# quasi_nano_led.net
KiCad netlist of a schematic drawn in EAGLE
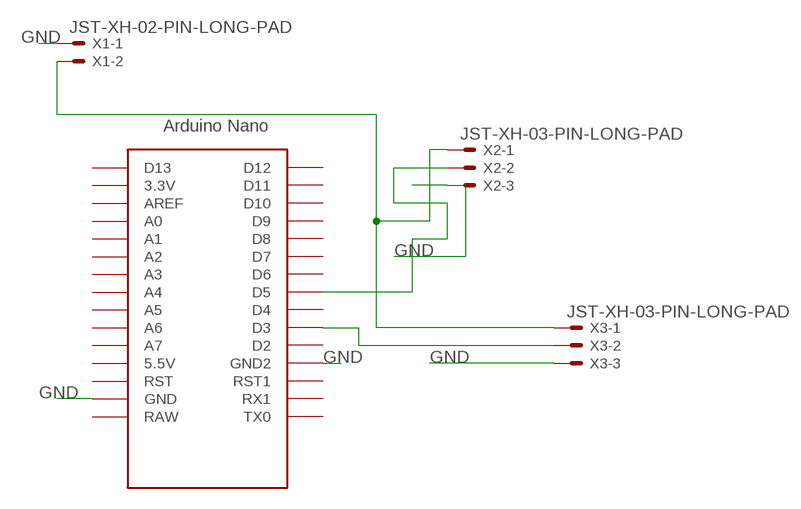
[diagram p0: schematic, sheet 1]

(export (version "E")
  (design (tool "Eeschema 10.0.6"))
  (components
    (comp (ref "U$1")
      (value "NANO")
      (footprint "eagle-import:NANO")
      (libsource (lib "eagle-import") (part "NANO"))
    )
    (comp (ref "X1")
      (value "JST-XH-02-PIN-LONG-PAD")
      (footprint "eagle-import:JST-XH-02-PACKAGE-LONG-PAD")
      (libsource (lib "eagle-import") (part "JST-XH-02-PIN-LONG-PAD"))
    )
    (comp (ref "X2")
      (value "JST-XH-03-PIN-LONG-PAD")
      (footprint "eagle-import:JST-XH-03-PACKAGE-LONG-PAD")
      (libsource (lib "eagle-import") (part "JST-XH-03-PIN-LONG-PAD"))
    )
    (comp (ref "X3")
      (value "JST-XH-03-PIN-LONG-PAD")
      (footprint "eagle-import:JST-XH-03-PACKAGE-LONG-PAD")
      (libsource (lib "eagle-import") (part "JST-XH-03-PIN-LONG-PAD"))
    )
  )
  (nets
    (net (code "1") (name "/GND") (class "Default")
      (node (ref "U$1") (pin "GND") (pinfunction "GND_GND") (pintype "bidirectional"))
      (node (ref "U$1") (pin "GND1") (pinfunction "GND2_GND1") (pintype "bidirectional"))
      (node (ref "X1") (pin "1") (pinfunction "S_1") (pintype "passive"))
      (node (ref "X2") (pin "3") (pinfunction "S_3") (pintype "passive"))
      (node (ref "X3") (pin "3") (pinfunction "S_3") (pintype "passive"))
    )
    (net (code "2") (name "Net-(X1B-S)") (class "Default")
      (node (ref "X1") (pin "2") (pinfunction "S_2") (pintype "passive"))
      (node (ref "X2") (pin "1") (pinfunction "S_1") (pintype "passive"))
      (node (ref "X3") (pin "1") (pinfunction "S_1") (pintype "passive"))
    )
    (net (code "3") (name "Net-(X2B-S)") (class "Default")
      (node (ref "U$1") (pin "D5") (pinfunction "D5_D5") (pintype "bidirectional"))
      (node (ref "X2") (pin "2") (pinfunction "S_2") (pintype "passive"))
    )
    (net (code "4") (name "Net-(X3B-S)") (class "Default")
      (node (ref "U$1") (pin "D3") (pinfunction "D3_D3") (pintype "bidirectional"))
      (node (ref "X3") (pin "2") (pinfunction "S_2") (pintype "passive"))
    )
    (net (code "5") (name "unconnected-(U$1-5.5V-Pad5V)") (class "Default")
      (node (ref "U$1") (pin "5V") (pinfunction "5.5V_5V") (pintype "bidirectional"))
    )
    (net (code "6") (name "unconnected-(U$1-Pad3.3V)") (class "Default")
      (node (ref "U$1") (pin "3.3V") (pinfunction "3.3V_3.3V") (pintype "bidirectional"))
    )
    (net (code "7") (name "unconnected-(U$1-PadA0)") (class "Default")
      (node (ref "U$1") (pin "A0") (pinfunction "A0_A0") (pintype "bidirectional"))
    )
    (net (code "8") (name "unconnected-(U$1-PadA1)") (class "Default")
      (node (ref "U$1") (pin "A1") (pinfunction "A1_A1") (pintype "bidirectional"))
    )
    (net (code "9") (name "unconnected-(U$1-PadA2)") (class "Default")
      (node (ref "U$1") (pin "A2") (pinfunction "A2_A2") (pintype "bidirectional"))
    )
    (net (code "10") (name "unconnected-(U$1-PadA3)") (class "Default")
      (node (ref "U$1") (pin "A3") (pinfunction "A3_A3") (pintype "bidirectional"))
    )
    (net (code "11") (name "unconnected-(U$1-PadA4)") (class "Default")
      (node (ref "U$1") (pin "A4") (pinfunction "A4_A4") (pintype "bidirectional"))
    )
    (net (code "12") (name "unconnected-(U$1-PadA5)") (class "Default")
      (node (ref "U$1") (pin "A5") (pinfunction "A5_A5") (pintype "bidirectional"))
    )
    (net (code "13") (name "unconnected-(U$1-PadA6)") (class "Default")
      (node (ref "U$1") (pin "A6") (pinfunction "A6_A6") (pintype "bidirectional"))
    )
    (net (code "14") (name "unconnected-(U$1-PadA7)") (class "Default")
      (node (ref "U$1") (pin "A7") (pinfunction "A7_A7") (pintype "bidirectional"))
    )
    (net (code "15") (name "unconnected-(U$1-PadAREF)") (class "Default")
      (node (ref "U$1") (pin "AREF") (pinfunction "AREF_AREF") (pintype "bidirectional"))
    )
    (net (code "16") (name "unconnected-(U$1-PadD2)") (class "Default")
      (node (ref "U$1") (pin "D2") (pinfunction "D2_D2") (pintype "bidirectional"))
    )
    (net (code "17") (name "unconnected-(U$1-PadD4)") (class "Default")
      (node (ref "U$1") (pin "D4") (pinfunction "D4_D4") (pintype "bidirectional"))
    )
    (net (code "18") (name "unconnected-(U$1-PadD6)") (class "Default")
      (node (ref "U$1") (pin "D6") (pinfunction "D6_D6") (pintype "bidirectional"))
    )
    (net (code "19") (name "unconnected-(U$1-PadD7)") (class "Default")
      (node (ref "U$1") (pin "D7") (pinfunction "D7_D7") (pintype "bidirectional"))
    )
    (net (code "20") (name "unconnected-(U$1-PadD8)") (class "Default")
      (node (ref "U$1") (pin "D8") (pinfunction "D8_D8") (pintype "bidirectional"))
    )
    (net (code "21") (name "unconnected-(U$1-PadD9)") (class "Default")
      (node (ref "U$1") (pin "D9") (pinfunction "D9_D9") (pintype "bidirectional"))
    )
    (net (code "22") (name "unconnected-(U$1-PadD10)") (class "Default")
      (node (ref "U$1") (pin "D10") (pinfunction "D10_D10") (pintype "bidirectional"))
    )
    (net (code "23") (name "unconnected-(U$1-PadD11)") (class "Default")
      (node (ref "U$1") (pin "D11") (pinfunction "D11_D11") (pintype "bidirectional"))
    )
    (net (code "24") (name "unconnected-(U$1-PadD12)") (class "Default")
      (node (ref "U$1") (pin "D12") (pinfunction "D12_D12") (pintype "bidirectional"))
    )
    (net (code "25") (name "unconnected-(U$1-PadD13)") (class "Default")
      (node (ref "U$1") (pin "D13") (pinfunction "D13_D13") (pintype "bidirectional"))
    )
    (net (code "26") (name "unconnected-(U$1-PadICSP1)") (class "Default")
      (node (ref "U$1") (pin "ICSP1") (pinfunction "ICSP1_ICSP1") (pintype "bidirectional"))
    )
    (net (code "27") (name "unconnected-(U$1-PadICSP2)") (class "Default")
      (node (ref "U$1") (pin "ICSP2") (pinfunction "ICSP2_ICSP2") (pintype "bidirectional"))
    )
    (net (code "28") (name "unconnected-(U$1-PadICSP3)") (class "Default")
      (node (ref "U$1") (pin "ICSP3") (pinfunction "ICSP3_ICSP3") (pintype "bidirectional"))
    )
    (net (code "29") (name "unconnected-(U$1-PadICSP4)") (class "Default")
      (node (ref "U$1") (pin "ICSP4") (pinfunction "ICSP4_ICSP4") (pintype "bidirectional"))
    )
    (net (code "30") (name "unconnected-(U$1-PadICSP5)") (class "Default")
      (node (ref "U$1") (pin "ICSP5") (pinfunction "ICSP5_ICSP5") (pintype "bidirectional"))
    )
    (net (code "31") (name "unconnected-(U$1-PadICSP6)") (class "Default")
      (node (ref "U$1") (pin "ICSP6") (pinfunction "ICSP6_ICSP6") (pintype "bidirectional"))
    )
    (net (code "32") (name "unconnected-(U$1-PadRAW)") (class "Default")
      (node (ref "U$1") (pin "RAW") (pinfunction "RAW_RAW") (pintype "bidirectional"))
    )
    (net (code "33") (name "unconnected-(U$1-PadRST)") (class "Default")
      (node (ref "U$1") (pin "RST") (pinfunction "RST_RST") (pintype "bidirectional"))
    )
    (net (code "34") (name "unconnected-(U$1-PadRST1)") (class "Default")
      (node (ref "U$1") (pin "RST1") (pinfunction "RST1_RST1") (pintype "bidirectional"))
    )
    (net (code "35") (name "unconnected-(U$1-PadRX1)") (class "Default")
      (node (ref "U$1") (pin "RX1") (pinfunction "RX1_RX1") (pintype "bidirectional"))
    )
    (net (code "36") (name "unconnected-(U$1-PadTX0)") (class "Default")
      (node (ref "U$1") (pin "TX0") (pinfunction "TX0_TX0") (pintype "bidirectional"))
    )
  )
)
